# 100_PowerSupply.net
KiCad netlist of a schematic drawn in Altium Designer
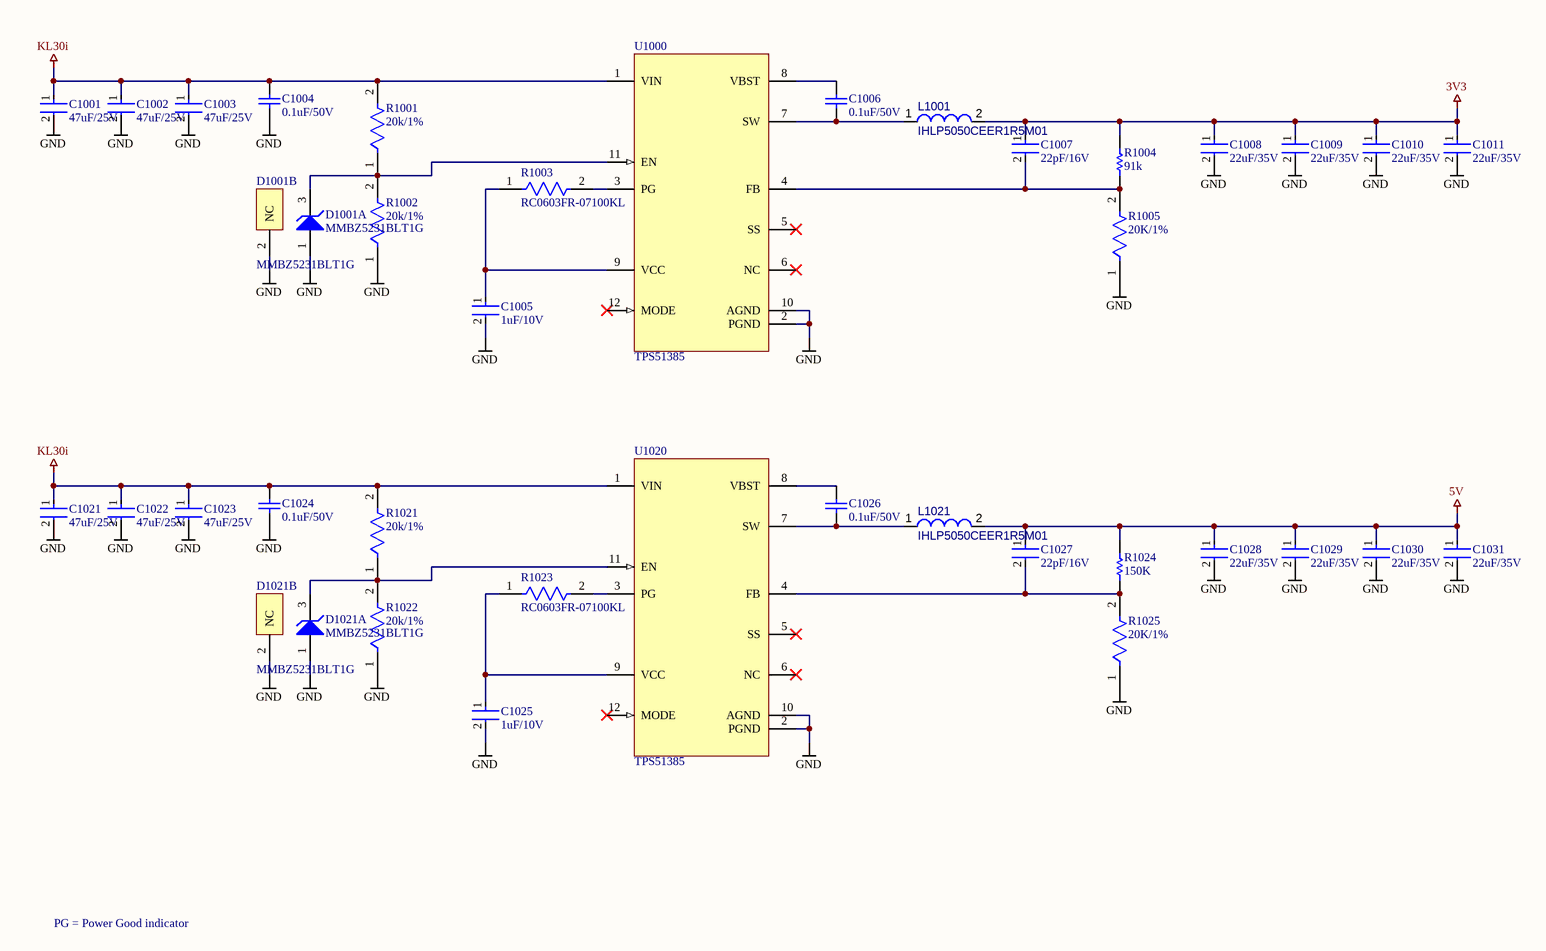
[diagram p0: 100_PowerSupply.SchDoc]

(export (version "E")
  (design (tool "Eeschema 10.0.6"))
  (components
    (comp (ref "C1001")
      (value "47uF/25V")
      (footprint "FP-C3216-160-0_2-MFG")
      (description "Multilayer Ceramic Capacitors 47uF ±20% 25V X5R SMD 1206\r\nC3216X5R1E476M160AC")
      (fields (field (name "VOLTAGE") "25V") (field (name "TOLERANCE") "20%"))
      (libsource (lib "Altium Content Vault") (part "11868f565c42a9108669ba33697ecf6"))
    )
    (comp (ref "C1002")
      (value "47uF/25V")
      (footprint "FP-C3216-160-0_2-MFG")
      (description "Multilayer Ceramic Capacitors 47uF ±20% 25V X5R SMD 1206\r\nC3216X5R1E476M160AC")
      (fields (field (name "VOLTAGE") "25V") (field (name "TOLERANCE") "20%"))
      (libsource (lib "Altium Content Vault") (part "11868f565c42a9108669ba33697ecf6"))
    )
    (comp (ref "C1003")
      (value "47uF/25V")
      (footprint "FP-C3216-160-0_2-MFG")
      (description "Multilayer Ceramic Capacitors 47uF ±20% 25V X5R SMD 1206\r\nC3216X5R1E476M160AC")
      (fields (field (name "VOLTAGE") "25V") (field (name "TOLERANCE") "20%"))
      (libsource (lib "Altium Content Vault") (part "11868f565c42a9108669ba33697ecf6"))
    )
    (comp (ref "C1004")
      (value "0.1uF/50V")
      (footprint "CAPC2013X135X45ML10T25")
      (fields
        (field (name "VOLTAGE") "50V")
        (field (name "TOLERANCE") "10%")
        (field (name "MANUFACTURER") "Murata")
      )
      (libsource (lib "Altium Content Vault") (part "CAP-NP-2"))
    )
    (comp (ref "C1005")
      (value "1uF/10V")
      (footprint "FP-C0603-CG-MFG")
      (description "CAP CER 1UF 10V Y5V 0603\r\nC0603C105Z8VACTU")
      (fields (field (name "TOLERANCE") "80%"))
      (libsource (lib "Altium Content Vault") (part "02cd4be3c70576c341d710602a673aa"))
    )
    (comp (ref "C1006")
      (value "0.1uF/50V")
      (footprint "CAPC2013X135X45ML10T25")
      (fields
        (field (name "VOLTAGE") "50V")
        (field (name "TOLERANCE") "10%")
        (field (name "MANUFACTURER") "Murata")
      )
      (libsource (lib "Altium Content Vault") (part "CAP-NP-2"))
    )
    (comp (ref "C1007")
      (value "22pF/16V")
      (footprint "FP-C0603C-CF-MFG")
      (description "CAP CER 22PF 16V 10% NP0 0603\r\nC0603C220K4GACTU")
      (fields (field (name "TOLERANCE") "0.1") (field (name "MANUFACTURER PART NUMBER") "C0603C220K4GACTU"))
      (libsource (lib "Altium Content Vault") (part "b4654b650e69147ec39a6b967a45e02"))
    )
    (comp (ref "C1008")
      (value "22uF/35V")
      (footprint "FP-C3216-160-0_2-IPC_B")
      (description "Multilayer Ceramic Capacitors 22uF ±20% 35V X5R SMD 1206\r\nC3216X5R1V226M160AC")
      (fields (field (name "TOLERANCE") "20%") (field (name "VOLTAGE") "35V"))
      (libsource (lib "Altium Content Vault") (part "11868f565c42a9108669ba33697ecf6"))
    )
    (comp (ref "C1009")
      (value "22uF/35V")
      (footprint "FP-C3216-160-0_2-IPC_B")
      (description "Multilayer Ceramic Capacitors 22uF ±20% 35V X5R SMD 1206\r\nC3216X5R1V226M160AC")
      (fields (field (name "TOLERANCE") "20%") (field (name "VOLTAGE") "35V"))
      (libsource (lib "Altium Content Vault") (part "11868f565c42a9108669ba33697ecf6"))
    )
    (comp (ref "C1010")
      (value "22uF/35V")
      (footprint "FP-C3216-160-0_2-IPC_B")
      (description "Multilayer Ceramic Capacitors 22uF ±20% 35V X5R SMD 1206\r\nC3216X5R1V226M160AC")
      (fields (field (name "TOLERANCE") "20%") (field (name "VOLTAGE") "35V"))
      (libsource (lib "Altium Content Vault") (part "11868f565c42a9108669ba33697ecf6"))
    )
    (comp (ref "C1011")
      (value "22uF/35V")
      (footprint "FP-C3216-160-0_2-IPC_B")
      (description "Multilayer Ceramic Capacitors 22uF ±20% 35V X5R SMD 1206\r\nC3216X5R1V226M160AC")
      (fields (field (name "TOLERANCE") "20%") (field (name "VOLTAGE") "35V"))
      (libsource (lib "Altium Content Vault") (part "11868f565c42a9108669ba33697ecf6"))
    )
    (comp (ref "C1021")
      (value "47uF/25V")
      (footprint "FP-C3216-160-0_2-MFG")
      (description "Multilayer Ceramic Capacitors 47uF ±20% 25V X5R SMD 1206\r\nC3216X5R1E476M160AC")
      (fields (field (name "VOLTAGE") "25V") (field (name "TOLERANCE") "20%"))
      (libsource (lib "Altium Content Vault") (part "11868f565c42a9108669ba33697ecf6"))
    )
    (comp (ref "C1022")
      (value "47uF/25V")
      (footprint "FP-C3216-160-0_2-MFG")
      (description "Multilayer Ceramic Capacitors 47uF ±20% 25V X5R SMD 1206\r\nC3216X5R1E476M160AC")
      (fields (field (name "VOLTAGE") "25V") (field (name "TOLERANCE") "20%"))
      (libsource (lib "Altium Content Vault") (part "11868f565c42a9108669ba33697ecf6"))
    )
    (comp (ref "C1023")
      (value "47uF/25V")
      (footprint "FP-C3216-160-0_2-MFG")
      (description "Multilayer Ceramic Capacitors 47uF ±20% 25V X5R SMD 1206\r\nC3216X5R1E476M160AC")
      (fields (field (name "VOLTAGE") "25V") (field (name "TOLERANCE") "20%"))
      (libsource (lib "Altium Content Vault") (part "11868f565c42a9108669ba33697ecf6"))
    )
    (comp (ref "C1024")
      (value "0.1uF/50V")
      (footprint "CAPC2013X135X45ML10T25")
      (fields
        (field (name "VOLTAGE") "50V")
        (field (name "TOLERANCE") "10%")
        (field (name "MANUFACTURER") "Murata")
      )
      (libsource (lib "Altium Content Vault") (part "CAP-NP-2"))
    )
    (comp (ref "C1025")
      (value "1uF/10V")
      (footprint "FP-C0603-CG-MFG")
      (description "CAP CER 1UF 10V Y5V 0603\r\nC0603C105Z8VACTU")
      (fields (field (name "TOLERANCE") "80%"))
      (libsource (lib "Altium Content Vault") (part "02cd4be3c70576c341d710602a673aa"))
    )
    (comp (ref "C1026")
      (value "0.1uF/50V")
      (footprint "CAPC2013X135X45ML10T25")
      (fields
        (field (name "VOLTAGE") "50V")
        (field (name "TOLERANCE") "10%")
        (field (name "MANUFACTURER") "Murata")
      )
      (libsource (lib "Altium Content Vault") (part "CAP-NP-2"))
    )
    (comp (ref "C1027")
      (value "22pF/16V")
      (footprint "FP-C0603C-CF-MFG")
      (description "CAP CER 22PF 16V 10% NP0 0603\r\nC0603C220K4GACTU")
      (fields (field (name "TOLERANCE") "0.1") (field (name "MANUFACTURER PART NUMBER") "C0603C220K4GACTU"))
      (libsource (lib "Altium Content Vault") (part "b4654b650e69147ec39a6b967a45e02"))
    )
    (comp (ref "C1028")
      (value "22uF/35V")
      (footprint "FP-C3216-160-0_2-IPC_B")
      (description "Multilayer Ceramic Capacitors 22uF ±20% 35V X5R SMD 1206\r\nC3216X5R1V226M160AC")
      (fields (field (name "TOLERANCE") "20%") (field (name "VOLTAGE") "35V"))
      (libsource (lib "Altium Content Vault") (part "11868f565c42a9108669ba33697ecf6"))
    )
    (comp (ref "C1029")
      (value "22uF/35V")
      (footprint "FP-C3216-160-0_2-IPC_B")
      (description "Multilayer Ceramic Capacitors 22uF ±20% 35V X5R SMD 1206\r\nC3216X5R1V226M160AC")
      (fields (field (name "TOLERANCE") "20%") (field (name "VOLTAGE") "35V"))
      (libsource (lib "Altium Content Vault") (part "11868f565c42a9108669ba33697ecf6"))
    )
    (comp (ref "C1030")
      (value "22uF/35V")
      (footprint "FP-C3216-160-0_2-IPC_B")
      (description "Multilayer Ceramic Capacitors 22uF ±20% 35V X5R SMD 1206\r\nC3216X5R1V226M160AC")
      (fields (field (name "TOLERANCE") "20%") (field (name "VOLTAGE") "35V"))
      (libsource (lib "Altium Content Vault") (part "11868f565c42a9108669ba33697ecf6"))
    )
    (comp (ref "C1031")
      (value "22uF/35V")
      (footprint "FP-C3216-160-0_2-IPC_B")
      (description "Multilayer Ceramic Capacitors 22uF ±20% 35V X5R SMD 1206\r\nC3216X5R1V226M160AC")
      (fields (field (name "TOLERANCE") "20%") (field (name "VOLTAGE") "35V"))
      (libsource (lib "Altium Content Vault") (part "11868f565c42a9108669ba33697ecf6"))
    )
    (comp (ref "D1001")
      (value "MMBZ5231BLT1G")
      (footprint "ONSC-SOT-23-3-318-08_V")
      (description "Zener Voltage Regulator, 225 mW, 3-Pin SOT-23, Pb-Free, Tape and Reel")
      (fields (field (name "MANUFACTURER") "On Semiconductor"))
      (libsource (lib "Altium Content Vault") (part "ONSC-A1K3-3"))
    )
    (comp (ref "D1021")
      (value "MMBZ5231BLT1G")
      (footprint "ONSC-SOT-23-3-318-08_V")
      (description "Zener Voltage Regulator, 225 mW, 3-Pin SOT-23, Pb-Free, Tape and Reel")
      (fields (field (name "MANUFACTURER") "On Semiconductor"))
      (libsource (lib "Altium Content Vault") (part "ONSC-A1K3-3"))
    )
    (comp (ref "L1001")
      (value "IHLP5050CEER1R5M01")
      (footprint "IHLP5050CEER1R5M01")
      (description "Chip Inductor, 1.5 uH, +/- 20%\r\nIHLP5050CEER1R5M01")
      (libsource (lib "AltiumLib_MILUTIN") (part "IHLP5050CEER1R5M01"))
    )
    (comp (ref "L1021")
      (value "IHLP5050CEER1R5M01")
      (footprint "IHLP5050CEER1R5M01")
      (description "Chip Inductor, 1.5 uH, +/- 20%\r\nIHLP5050CEER1R5M01")
      (libsource (lib "AltiumLib_MILUTIN") (part "IHLP5050CEER1R5M01"))
    )
    (comp (ref "R1001")
      (value "20k/1%")
      (footprint "FP-RC0603-0_55-IPC_C")
      (description "RES 20K OHM 1% 1/10W 0603\r\nRC0603FR-0720KL")
      (fields (field (name "TOLERANCE") "1%"))
      (libsource (lib "Altium Content Vault") (part "1029c3af85768c4190bb7ad29bc67b5"))
    )
    (comp (ref "R1002")
      (value "20k/1%")
      (footprint "FP-RC0603-0_55-IPC_C")
      (description "RES 20K OHM 1% 1/10W 0603\r\nRC0603FR-0720KL")
      (fields (field (name "TOLERANCE") "1%"))
      (libsource (lib "Altium Content Vault") (part "1029c3af85768c4190bb7ad29bc67b5"))
    )
    (comp (ref "R1003")
      (value "RC0603FR-07100KL")
      (footprint "FP-RC0603-0_55-MFG")
      (description "RES SMD 100K OHM 1% 1/10W 0603")
      (fields (field (name "TOLERANCE") "1%"))
      (libsource (lib "Altium Content Vault") (part "1029c3af85768c4190bb7ad29bc67b5"))
    )
    (comp (ref "R1004")
      (value "91k")
      (footprint "RESC1609X50X30NL10T20")
      (description "CRCW060391K0FKEA")
      (fields (field (name "MANUFACTURER") "Vishay Dale"))
      (libsource (lib "Altium Content Vault") (part "RES"))
    )
    (comp (ref "R1005")
      (value "20K/1%")
      (footprint "FP-RC0603-0_55-IPC_C")
      (description "RES 20K OHM 1% 1/10W 0603\r\nRC0603FR-0720KL")
      (fields (field (name "TOLERANCE") "1%"))
      (libsource (lib "Altium Content Vault") (part "1029c3af85768c4190bb7ad29bc67b5"))
    )
    (comp (ref "R1021")
      (value "20k/1%")
      (footprint "FP-RC0603-0_55-IPC_C")
      (description "RES 20K OHM 1% 1/10W 0603\r\nRC0603FR-0720KL")
      (fields (field (name "TOLERANCE") "1%"))
      (libsource (lib "Altium Content Vault") (part "1029c3af85768c4190bb7ad29bc67b5"))
    )
    (comp (ref "R1022")
      (value "20k/1%")
      (footprint "FP-RC0603-0_55-IPC_C")
      (description "RES 20K OHM 1% 1/10W 0603\r\nRC0603FR-0720KL")
      (fields (field (name "TOLERANCE") "1%"))
      (libsource (lib "Altium Content Vault") (part "1029c3af85768c4190bb7ad29bc67b5"))
    )
    (comp (ref "R1023")
      (value "RC0603FR-07100KL")
      (footprint "FP-RC0603-0_55-MFG")
      (description "RES SMD 100K OHM 1% 1/10W 0603")
      (fields (field (name "TOLERANCE") "1%"))
      (libsource (lib "Altium Content Vault") (part "1029c3af85768c4190bb7ad29bc67b5"))
    )
    (comp (ref "R1024")
      (value "150K")
      (footprint "RESC1608X55X30NL15T15")
      (description "ERJ-3EKF1503V")
      (fields (field (name "MANUFACTURER") "Panasonic"))
      (libsource (lib "Altium Content Vault") (part "RES"))
    )
    (comp (ref "R1025")
      (value "20K/1%")
      (footprint "FP-RC0603-0_55-IPC_C")
      (description "RES 20K OHM 1% 1/10W 0603\r\nRC0603FR-0720KL")
      (fields (field (name "TOLERANCE") "1%"))
      (libsource (lib "Altium Content Vault") (part "1029c3af85768c4190bb7ad29bc67b5"))
    )
    (comp (ref "U1000")
      (value "TPS51385")
      (footprint "TPS51386")
      (description "8A Synchronous Buck Converter - TPS51386")
      (libsource (lib "AltiumLib_MILUTIN") (part "TPS51386"))
    )
    (comp (ref "U1020")
      (value "TPS51385")
      (footprint "TPS51386")
      (description "8A Synchronous Buck Converter - TPS51386")
      (libsource (lib "AltiumLib_MILUTIN") (part "TPS51386"))
    )
  )
  (nets
    (net (code "1") (name "3V3") (class "Default")
      (node (ref "C1007") (pin "1") (pinfunction "1_1") (pintype "passive"))
      (node (ref "C1008") (pin "1") (pinfunction "1_1") (pintype "passive"))
      (node (ref "C1009") (pin "1") (pinfunction "1_1") (pintype "passive"))
      (node (ref "C1010") (pin "1") (pinfunction "1_1") (pintype "passive"))
      (node (ref "C1011") (pin "1") (pinfunction "1_1") (pintype "passive"))
      (node (ref "L1001") (pin "2") (pinfunction "2_2") (pintype "passive"))
      (node (ref "R1004") (pin "2") (pinfunction "2_2") (pintype "passive"))
    )
    (net (code "2") (name "5V") (class "Default")
      (node (ref "C1027") (pin "1") (pinfunction "1_1") (pintype "passive"))
      (node (ref "C1028") (pin "1") (pinfunction "1_1") (pintype "passive"))
      (node (ref "C1029") (pin "1") (pinfunction "1_1") (pintype "passive"))
      (node (ref "C1030") (pin "1") (pinfunction "1_1") (pintype "passive"))
      (node (ref "C1031") (pin "1") (pinfunction "1_1") (pintype "passive"))
      (node (ref "L1021") (pin "2") (pinfunction "2_2") (pintype "passive"))
      (node (ref "R1024") (pin "2") (pinfunction "2_2") (pintype "passive"))
    )
    (net (code "3") (name "GND") (class "Default")
      (node (ref "C1001") (pin "2") (pinfunction "2_2") (pintype "passive"))
      (node (ref "C1002") (pin "2") (pinfunction "2_2") (pintype "passive"))
      (node (ref "C1003") (pin "2") (pinfunction "2_2") (pintype "passive"))
      (node (ref "C1004") (pin "1") (pinfunction "1_1") (pintype "passive"))
      (node (ref "C1005") (pin "2") (pinfunction "2_2") (pintype "passive"))
      (node (ref "C1008") (pin "2") (pinfunction "2_2") (pintype "passive"))
      (node (ref "C1009") (pin "2") (pinfunction "2_2") (pintype "passive"))
      (node (ref "C1010") (pin "2") (pinfunction "2_2") (pintype "passive"))
      (node (ref "C1011") (pin "2") (pinfunction "2_2") (pintype "passive"))
      (node (ref "C1021") (pin "2") (pinfunction "2_2") (pintype "passive"))
      (node (ref "C1022") (pin "2") (pinfunction "2_2") (pintype "passive"))
      (node (ref "C1023") (pin "2") (pinfunction "2_2") (pintype "passive"))
      (node (ref "C1024") (pin "1") (pinfunction "1_1") (pintype "passive"))
      (node (ref "C1025") (pin "2") (pinfunction "2_2") (pintype "passive"))
      (node (ref "C1028") (pin "2") (pinfunction "2_2") (pintype "passive"))
      (node (ref "C1029") (pin "2") (pinfunction "2_2") (pintype "passive"))
      (node (ref "C1030") (pin "2") (pinfunction "2_2") (pintype "passive"))
      (node (ref "C1031") (pin "2") (pinfunction "2_2") (pintype "passive"))
      (node (ref "D1001") (pin "1") (pinfunction "A_1") (pintype "passive"))
      (node (ref "D1001") (pin "2") (pinfunction "NC_2") (pintype "passive"))
      (node (ref "D1021") (pin "1") (pinfunction "A_1") (pintype "passive"))
      (node (ref "D1021") (pin "2") (pinfunction "NC_2") (pintype "passive"))
      (node (ref "R1002") (pin "1") (pinfunction "1_1") (pintype "passive"))
      (node (ref "R1005") (pin "1") (pinfunction "1_1") (pintype "passive"))
      (node (ref "R1022") (pin "1") (pinfunction "1_1") (pintype "passive"))
      (node (ref "R1025") (pin "1") (pinfunction "1_1") (pintype "passive"))
      (node (ref "U1000") (pin "10") (pinfunction "AGND_10") (pintype "passive"))
      (node (ref "U1000") (pin "2") (pinfunction "PGND_2") (pintype "passive"))
      (node (ref "U1020") (pin "10") (pinfunction "AGND_10") (pintype "passive"))
      (node (ref "U1020") (pin "2") (pinfunction "PGND_2") (pintype "passive"))
    )
    (net (code "4") (name "KL30i") (class "Default")
      (node (ref "C1001") (pin "1") (pinfunction "1_1") (pintype "passive"))
      (node (ref "C1002") (pin "1") (pinfunction "1_1") (pintype "passive"))
      (node (ref "C1003") (pin "1") (pinfunction "1_1") (pintype "passive"))
      (node (ref "C1004") (pin "2") (pinfunction "2_2") (pintype "passive"))
      (node (ref "C1021") (pin "1") (pinfunction "1_1") (pintype "passive"))
      (node (ref "C1022") (pin "1") (pinfunction "1_1") (pintype "passive"))
      (node (ref "C1023") (pin "1") (pinfunction "1_1") (pintype "passive"))
      (node (ref "C1024") (pin "2") (pinfunction "2_2") (pintype "passive"))
      (node (ref "R1001") (pin "2") (pinfunction "2_2") (pintype "passive"))
      (node (ref "R1021") (pin "2") (pinfunction "2_2") (pintype "passive"))
      (node (ref "U1000") (pin "1") (pinfunction "VIN_1") (pintype "passive"))
      (node (ref "U1020") (pin "1") (pinfunction "VIN_1") (pintype "passive"))
    )
    (net (code "5") (name "Net-(D1001A-K)") (class "Default")
      (node (ref "D1001") (pin "3") (pinfunction "K_3") (pintype "passive"))
      (node (ref "R1001") (pin "1") (pinfunction "1_1") (pintype "passive"))
      (node (ref "R1002") (pin "2") (pinfunction "2_2") (pintype "passive"))
      (node (ref "U1000") (pin "11") (pinfunction "EN_11") (pintype "input"))
    )
    (net (code "6") (name "Net-(D1021A-K)") (class "Default")
      (node (ref "D1021") (pin "3") (pinfunction "K_3") (pintype "passive"))
      (node (ref "R1021") (pin "1") (pinfunction "1_1") (pintype "passive"))
      (node (ref "R1022") (pin "2") (pinfunction "2_2") (pintype "passive"))
      (node (ref "U1020") (pin "11") (pinfunction "EN_11") (pintype "input"))
    )
    (net (code "7") (name "Net-(U1000-FB)") (class "Default")
      (node (ref "C1007") (pin "2") (pinfunction "2_2") (pintype "passive"))
      (node (ref "R1004") (pin "1") (pinfunction "1_1") (pintype "passive"))
      (node (ref "R1005") (pin "2") (pinfunction "2_2") (pintype "passive"))
      (node (ref "U1000") (pin "4") (pinfunction "FB_4") (pintype "passive"))
    )
    (net (code "8") (name "Net-(U1000-PG)") (class "Default")
      (node (ref "R1003") (pin "2") (pinfunction "2_2") (pintype "passive"))
      (node (ref "U1000") (pin "3") (pinfunction "PG_3") (pintype "passive"))
    )
    (net (code "9") (name "Net-(U1000-SW)") (class "Default")
      (node (ref "C1006") (pin "1") (pinfunction "1_1") (pintype "passive"))
      (node (ref "L1001") (pin "1") (pinfunction "1_1") (pintype "passive"))
      (node (ref "U1000") (pin "7") (pinfunction "SW_7") (pintype "passive"))
    )
    (net (code "10") (name "Net-(U1000-VBST)") (class "Default")
      (node (ref "C1006") (pin "2") (pinfunction "2_2") (pintype "passive"))
      (node (ref "U1000") (pin "8") (pinfunction "VBST_8") (pintype "passive"))
    )
    (net (code "11") (name "Net-(U1000-VCC)") (class "Default")
      (node (ref "C1005") (pin "1") (pinfunction "1_1") (pintype "passive"))
      (node (ref "R1003") (pin "1") (pinfunction "1_1") (pintype "passive"))
      (node (ref "U1000") (pin "9") (pinfunction "VCC_9") (pintype "passive"))
    )
    (net (code "12") (name "Net-(U1020-FB)") (class "Default")
      (node (ref "C1027") (pin "2") (pinfunction "2_2") (pintype "passive"))
      (node (ref "R1024") (pin "1") (pinfunction "1_1") (pintype "passive"))
      (node (ref "R1025") (pin "2") (pinfunction "2_2") (pintype "passive"))
      (node (ref "U1020") (pin "4") (pinfunction "FB_4") (pintype "passive"))
    )
    (net (code "13") (name "Net-(U1020-PG)") (class "Default")
      (node (ref "R1023") (pin "2") (pinfunction "2_2") (pintype "passive"))
      (node (ref "U1020") (pin "3") (pinfunction "PG_3") (pintype "passive"))
    )
    (net (code "14") (name "Net-(U1020-SW)") (class "Default")
      (node (ref "C1026") (pin "1") (pinfunction "1_1") (pintype "passive"))
      (node (ref "L1021") (pin "1") (pinfunction "1_1") (pintype "passive"))
      (node (ref "U1020") (pin "7") (pinfunction "SW_7") (pintype "passive"))
    )
    (net (code "15") (name "Net-(U1020-VBST)") (class "Default")
      (node (ref "C1026") (pin "2") (pinfunction "2_2") (pintype "passive"))
      (node (ref "U1020") (pin "8") (pinfunction "VBST_8") (pintype "passive"))
    )
    (net (code "16") (name "Net-(U1020-VCC)") (class "Default")
      (node (ref "C1025") (pin "1") (pinfunction "1_1") (pintype "passive"))
      (node (ref "R1023") (pin "1") (pinfunction "1_1") (pintype "passive"))
      (node (ref "U1020") (pin "9") (pinfunction "VCC_9") (pintype "passive"))
    )
    (net (code "17") (name "unconnected-(U1000-MODE-Pad12)") (class "Default")
      (node (ref "U1000") (pin "12") (pinfunction "MODE_12") (pintype "input+no_connect"))
    )
    (net (code "18") (name "unconnected-(U1000-NC-Pad6)") (class "Default")
      (node (ref "U1000") (pin "6") (pinfunction "NC_6") (pintype "passive+no_connect"))
    )
    (net (code "19") (name "unconnected-(U1000-SS-Pad5)") (class "Default")
      (node (ref "U1000") (pin "5") (pinfunction "SS_5") (pintype "passive+no_connect"))
    )
    (net (code "20") (name "unconnected-(U1020-MODE-Pad12)") (class "Default")
      (node (ref "U1020") (pin "12") (pinfunction "MODE_12") (pintype "input+no_connect"))
    )
    (net (code "21") (name "unconnected-(U1020-NC-Pad6)") (class "Default")
      (node (ref "U1020") (pin "6") (pinfunction "NC_6") (pintype "passive+no_connect"))
    )
    (net (code "22") (name "unconnected-(U1020-SS-Pad5)") (class "Default")
      (node (ref "U1020") (pin "5") (pinfunction "SS_5") (pintype "passive+no_connect"))
    )
  )
)
